# BeatDetect.net
KiCad netlist of a schematic drawn in EAGLE
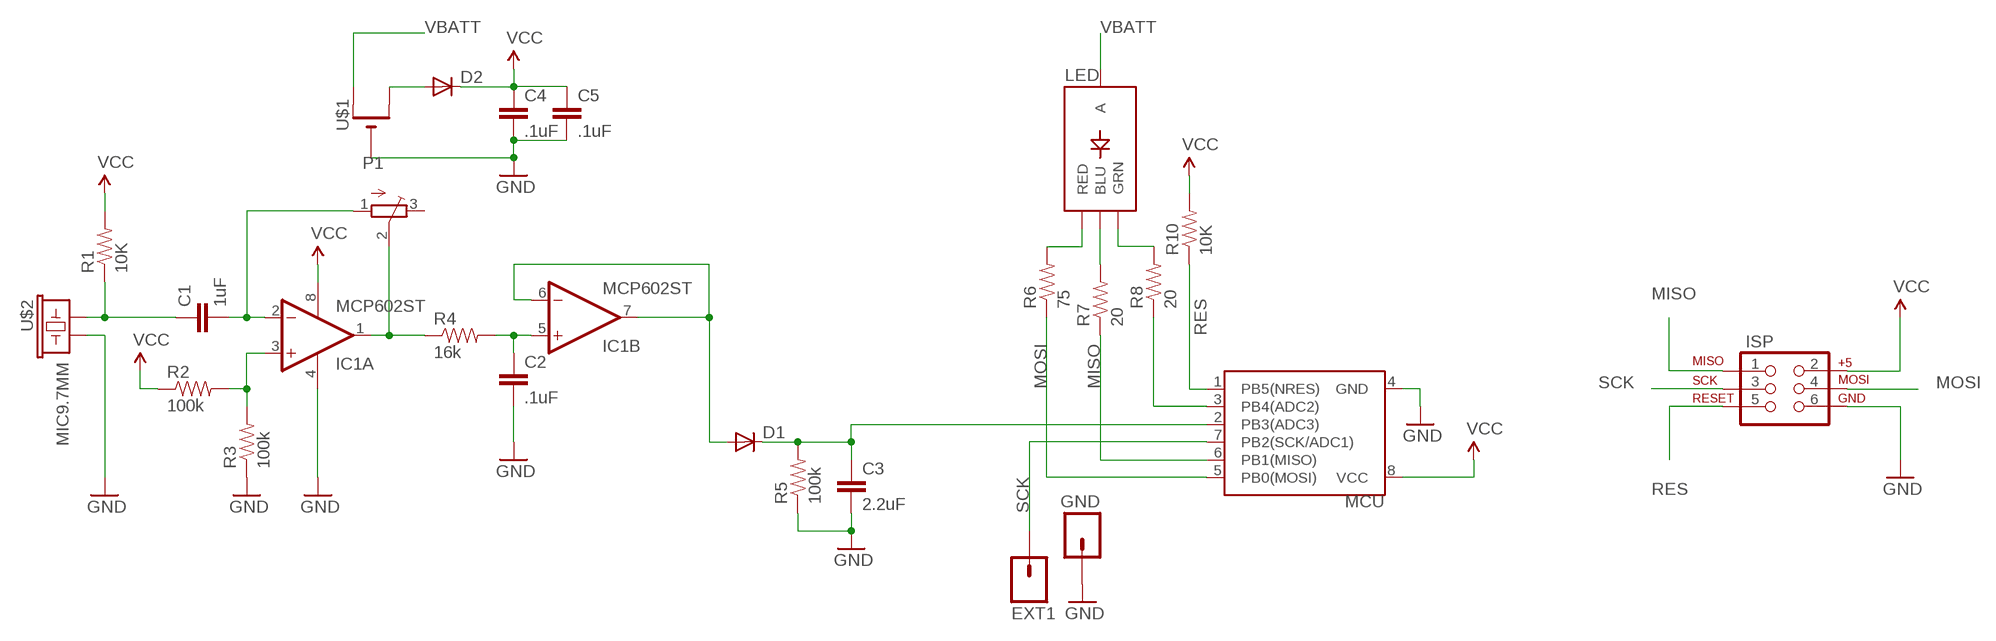
[diagram p0: schematic, sheet 1]

(export (version "E")
  (design (tool "Eeschema 10.0.6"))
  (components
    (comp (ref "C1")
      (value "1uF")
      (footprint "eagle-import:0805")
      (libsource (lib "eagle-import") (part "SparkFun-Passives_CAP0805"))
    )
    (comp (ref "C2")
      (value ".1uF")
      (footprint "eagle-import:0603-CAP")
      (libsource (lib "eagle-import") (part "SparkFun-Passives_CAP0603-CAP"))
    )
    (comp (ref "C3")
      (value "2.2uF")
      (footprint "eagle-import:0805")
      (libsource (lib "eagle-import") (part "CAP0805"))
    )
    (comp (ref "C4")
      (value ".1uF")
      (footprint "eagle-import:0603-CAP")
      (libsource (lib "eagle-import") (part "CAP0603-CAP"))
    )
    (comp (ref "C5")
      (value ".1uF")
      (footprint "eagle-import:0603-CAP")
      (libsource (lib "eagle-import") (part "CAP0603-CAP"))
    )
    (comp (ref "D1")
      (value "DIODESOD")
      (footprint "eagle-import:SOD-323")
      (libsource (lib "eagle-import") (part "DIODESOD"))
    )
    (comp (ref "D2")
      (value "DIODESOD")
      (footprint "eagle-import:SOD-323")
      (libsource (lib "eagle-import") (part "DIODESOD"))
    )
    (comp (ref "EXT1")
      (value "M01PTH")
      (footprint "eagle-import:1X01")
      (libsource (lib "eagle-import") (part "M01PTH"))
    )
    (comp (ref "GND")
      (value "M01PTH")
      (footprint "eagle-import:1X01")
      (libsource (lib "eagle-import") (part "M01PTH"))
    )
    (comp (ref "IC1")
      (value "MCP602ST")
      (footprint "eagle-import:TSSOP8")
      (libsource (lib "eagle-import") (part "MCP602ST"))
    )
    (comp (ref "ISP")
      (value "AVR_SPI_PRG_6PTH")
      (footprint "eagle-import:2X3")
      (libsource (lib "eagle-import") (part "AVR_SPI_PRG_6PTH"))
    )
    (comp (ref "LED")
      (value "LED-TRICOLORPLCC4")
      (footprint "eagle-import:LED-PLCC4")
      (libsource (lib "eagle-import") (part "LED-TRICOLORPLCC4"))
    )
    (comp (ref "MCU")
      (value "ATTINY45X")
      (footprint "eagle-import:TSSOP8")
      (libsource (lib "eagle-import") (part "ATTINY45X"))
    )
    (comp (ref "P1")
      (value "TRIMPOTTC33X")
      (footprint "eagle-import:TC33X")
      (libsource (lib "eagle-import") (part "TRIMPOTTC33X"))
    )
    (comp (ref "R1")
      (value "10K")
      (footprint "eagle-import:0402-RES")
      (libsource (lib "eagle-import") (part "RESISTOR0402-RES"))
    )
    (comp (ref "R2")
      (value "100k")
      (footprint "eagle-import:0402-RES")
      (libsource (lib "eagle-import") (part "RESISTOR0402-RES"))
    )
    (comp (ref "R3")
      (value "100k")
      (footprint "eagle-import:0402-RES")
      (libsource (lib "eagle-import") (part "RESISTOR0402-RES"))
    )
    (comp (ref "R4")
      (value "16k")
      (footprint "eagle-import:0402-RES")
      (libsource (lib "eagle-import") (part "RESISTOR0402-RES"))
    )
    (comp (ref "R5")
      (value "100k")
      (footprint "eagle-import:0402-RES")
      (libsource (lib "eagle-import") (part "RESISTOR0402-RES"))
    )
    (comp (ref "R6")
      (value "75")
      (footprint "eagle-import:0805")
      (libsource (lib "eagle-import") (part "RESISTOR0805-RES"))
    )
    (comp (ref "R7")
      (value "20")
      (footprint "eagle-import:0402-RES")
      (libsource (lib "eagle-import") (part "RESISTOR0402-RES"))
    )
    (comp (ref "R8")
      (value "20")
      (footprint "eagle-import:0402-RES")
      (libsource (lib "eagle-import") (part "RESISTOR0402-RES"))
    )
    (comp (ref "R10")
      (value "10K")
      (footprint "eagle-import:0402-RES")
      (libsource (lib "eagle-import") (part "RESISTOR0402-RES"))
    )
    (comp (ref "U$1")
      (value "CR2032SMT")
      (footprint "eagle-import:CR2032-SMD")
      (libsource (lib "eagle-import") (part "CR2032SMT"))
    )
    (comp (ref "U$2")
      (value "MIC9.7MM")
      (footprint "eagle-import:MIC-9.7MM")
      (libsource (lib "eagle-import") (part "MIC9.7MM"))
    )
  )
  (nets
    (net (code "1") (name "/MISO") (class "Default")
      (node (ref "ISP") (pin "1") (pinfunction "1_1") (pintype "passive"))
      (node (ref "MCU") (pin "6") (pinfunction "PB1(MISO)_6") (pintype "bidirectional"))
      (node (ref "R7") (pin "1") (pinfunction "1_1") (pintype "passive"))
    )
    (net (code "2") (name "/MOSI") (class "Default")
      (node (ref "ISP") (pin "4") (pinfunction "4_4") (pintype "passive"))
      (node (ref "MCU") (pin "5") (pinfunction "PB0(MOSI)_5") (pintype "bidirectional"))
      (node (ref "R6") (pin "1") (pinfunction "1_1") (pintype "passive"))
    )
    (net (code "3") (name "/RES") (class "Default")
      (node (ref "ISP") (pin "5") (pinfunction "5_5") (pintype "passive"))
      (node (ref "MCU") (pin "1") (pinfunction "PB5(NRES)_1") (pintype "bidirectional"))
      (node (ref "R10") (pin "1") (pinfunction "1_1") (pintype "passive"))
    )
    (net (code "4") (name "/SCK") (class "Default")
      (node (ref "EXT1") (pin "1") (pinfunction "1_1") (pintype "passive"))
      (node (ref "ISP") (pin "3") (pinfunction "3_3") (pintype "passive"))
      (node (ref "MCU") (pin "7") (pinfunction "PB2(SCK/ADC1)_7") (pintype "bidirectional"))
    )
    (net (code "5") (name "/VBATT") (class "Default")
      (node (ref "LED") (pin "A") (pinfunction "A_A") (pintype "bidirectional"))
      (node (ref "U$1") (pin "+$1") (pinfunction "+_+$1") (pintype "passive"))
    )
    (net (code "6") (name "GND") (class "Default")
      (node (ref "C2") (pin "2") (pinfunction "2_2") (pintype "passive"))
      (node (ref "C3") (pin "2") (pinfunction "2_2") (pintype "passive"))
      (node (ref "C4") (pin "2") (pinfunction "2_2") (pintype "passive"))
      (node (ref "C5") (pin "2") (pinfunction "2_2") (pintype "passive"))
      (node (ref "GND") (pin "1") (pinfunction "1_1") (pintype "passive"))
      (node (ref "IC1") (pin "4") (pinfunction "V-_4") (pintype "power_in"))
      (node (ref "ISP") (pin "6") (pinfunction "6_6") (pintype "passive"))
      (node (ref "MCU") (pin "4") (pinfunction "GND_4") (pintype "bidirectional"))
      (node (ref "R3") (pin "1") (pinfunction "1_1") (pintype "passive"))
      (node (ref "R5") (pin "1") (pinfunction "1_1") (pintype "passive"))
      (node (ref "U$1") (pin "-") (pinfunction "-_-") (pintype "passive"))
      (node (ref "U$2") (pin "2") (pinfunction "2_2") (pintype "passive"))
    )
    (net (code "7") (name "Net-(C1-Pad1)") (class "Default")
      (node (ref "C1") (pin "1") (pinfunction "1_1") (pintype "passive"))
      (node (ref "R1") (pin "1") (pinfunction "1_1") (pintype "passive"))
      (node (ref "U$2") (pin "1") (pinfunction "1_1") (pintype "passive"))
    )
    (net (code "8") (name "Net-(D1-A)") (class "Default")
      (node (ref "D1") (pin "2") (pinfunction "A_2") (pintype "passive"))
      (node (ref "IC1") (pin "6") (pinfunction "-IN_6") (pintype "input"))
      (node (ref "IC1") (pin "7") (pinfunction "OUT_7") (pintype "output"))
    )
    (net (code "9") (name "Net-(D1-C)") (class "Default")
      (node (ref "C3") (pin "1") (pinfunction "1_1") (pintype "passive"))
      (node (ref "D1") (pin "1") (pinfunction "C_1") (pintype "passive"))
      (node (ref "MCU") (pin "2") (pinfunction "PB3(ADC3)_2") (pintype "bidirectional"))
      (node (ref "R5") (pin "2") (pinfunction "2_2") (pintype "passive"))
    )
    (net (code "10") (name "Net-(D2-A)") (class "Default")
      (node (ref "D2") (pin "2") (pinfunction "A_2") (pintype "passive"))
      (node (ref "U$1") (pin "+$2") (pinfunction "+1_+$2") (pintype "passive"))
    )
    (net (code "11") (name "Net-(IC1A-+IN)") (class "Default")
      (node (ref "IC1") (pin "3") (pinfunction "+IN_3") (pintype "input"))
      (node (ref "R2") (pin "2") (pinfunction "2_2") (pintype "passive"))
      (node (ref "R3") (pin "2") (pinfunction "2_2") (pintype "passive"))
    )
    (net (code "12") (name "Net-(IC1A--IN)") (class "Default")
      (node (ref "C1") (pin "2") (pinfunction "2_2") (pintype "passive"))
      (node (ref "IC1") (pin "2") (pinfunction "-IN_2") (pintype "input"))
      (node (ref "P1") (pin "1") (pinfunction "A_1") (pintype "passive"))
    )
    (net (code "13") (name "Net-(IC1A-OUT)") (class "Default")
      (node (ref "IC1") (pin "1") (pinfunction "OUT_1") (pintype "output"))
      (node (ref "P1") (pin "2") (pinfunction "S_2") (pintype "passive"))
      (node (ref "R4") (pin "1") (pinfunction "1_1") (pintype "passive"))
    )
    (net (code "14") (name "Net-(IC1B-+IN)") (class "Default")
      (node (ref "C2") (pin "1") (pinfunction "1_1") (pintype "passive"))
      (node (ref "IC1") (pin "5") (pinfunction "+IN_5") (pintype "input"))
      (node (ref "R4") (pin "2") (pinfunction "2_2") (pintype "passive"))
    )
    (net (code "15") (name "Net-(LED-BLU)") (class "Default")
      (node (ref "LED") (pin "B") (pinfunction "BLU_B") (pintype "bidirectional"))
      (node (ref "R7") (pin "2") (pinfunction "2_2") (pintype "passive"))
    )
    (net (code "16") (name "Net-(LED-GRN)") (class "Default")
      (node (ref "LED") (pin "G") (pinfunction "GRN_G") (pintype "bidirectional"))
      (node (ref "R8") (pin "2") (pinfunction "2_2") (pintype "passive"))
    )
    (net (code "17") (name "Net-(LED-RED)") (class "Default")
      (node (ref "LED") (pin "R") (pinfunction "RED_R") (pintype "bidirectional"))
      (node (ref "R6") (pin "2") (pinfunction "2_2") (pintype "passive"))
    )
    (net (code "18") (name "Net-(MCU-PB4(ADC2))") (class "Default")
      (node (ref "MCU") (pin "3") (pinfunction "PB4(ADC2)_3") (pintype "bidirectional"))
      (node (ref "R8") (pin "1") (pinfunction "1_1") (pintype "passive"))
    )
    (net (code "19") (name "VCC") (class "Default")
      (node (ref "C4") (pin "1") (pinfunction "1_1") (pintype "passive"))
      (node (ref "C5") (pin "1") (pinfunction "1_1") (pintype "passive"))
      (node (ref "D2") (pin "1") (pinfunction "C_1") (pintype "passive"))
      (node (ref "IC1") (pin "8") (pinfunction "V+_8") (pintype "power_in"))
      (node (ref "ISP") (pin "2") (pinfunction "2_2") (pintype "passive"))
      (node (ref "MCU") (pin "8") (pinfunction "VCC_8") (pintype "bidirectional"))
      (node (ref "R1") (pin "2") (pinfunction "2_2") (pintype "passive"))
      (node (ref "R10") (pin "2") (pinfunction "2_2") (pintype "passive"))
      (node (ref "R2") (pin "1") (pinfunction "1_1") (pintype "passive"))
    )
    (net (code "20") (name "unconnected-(P1-E-Pad3)") (class "Default")
      (node (ref "P1") (pin "3") (pinfunction "E_3") (pintype "passive"))
    )
  )
)
